# 4_324_039__3_1.net
KiCad netlist of a schematic drawn in Altium Designer
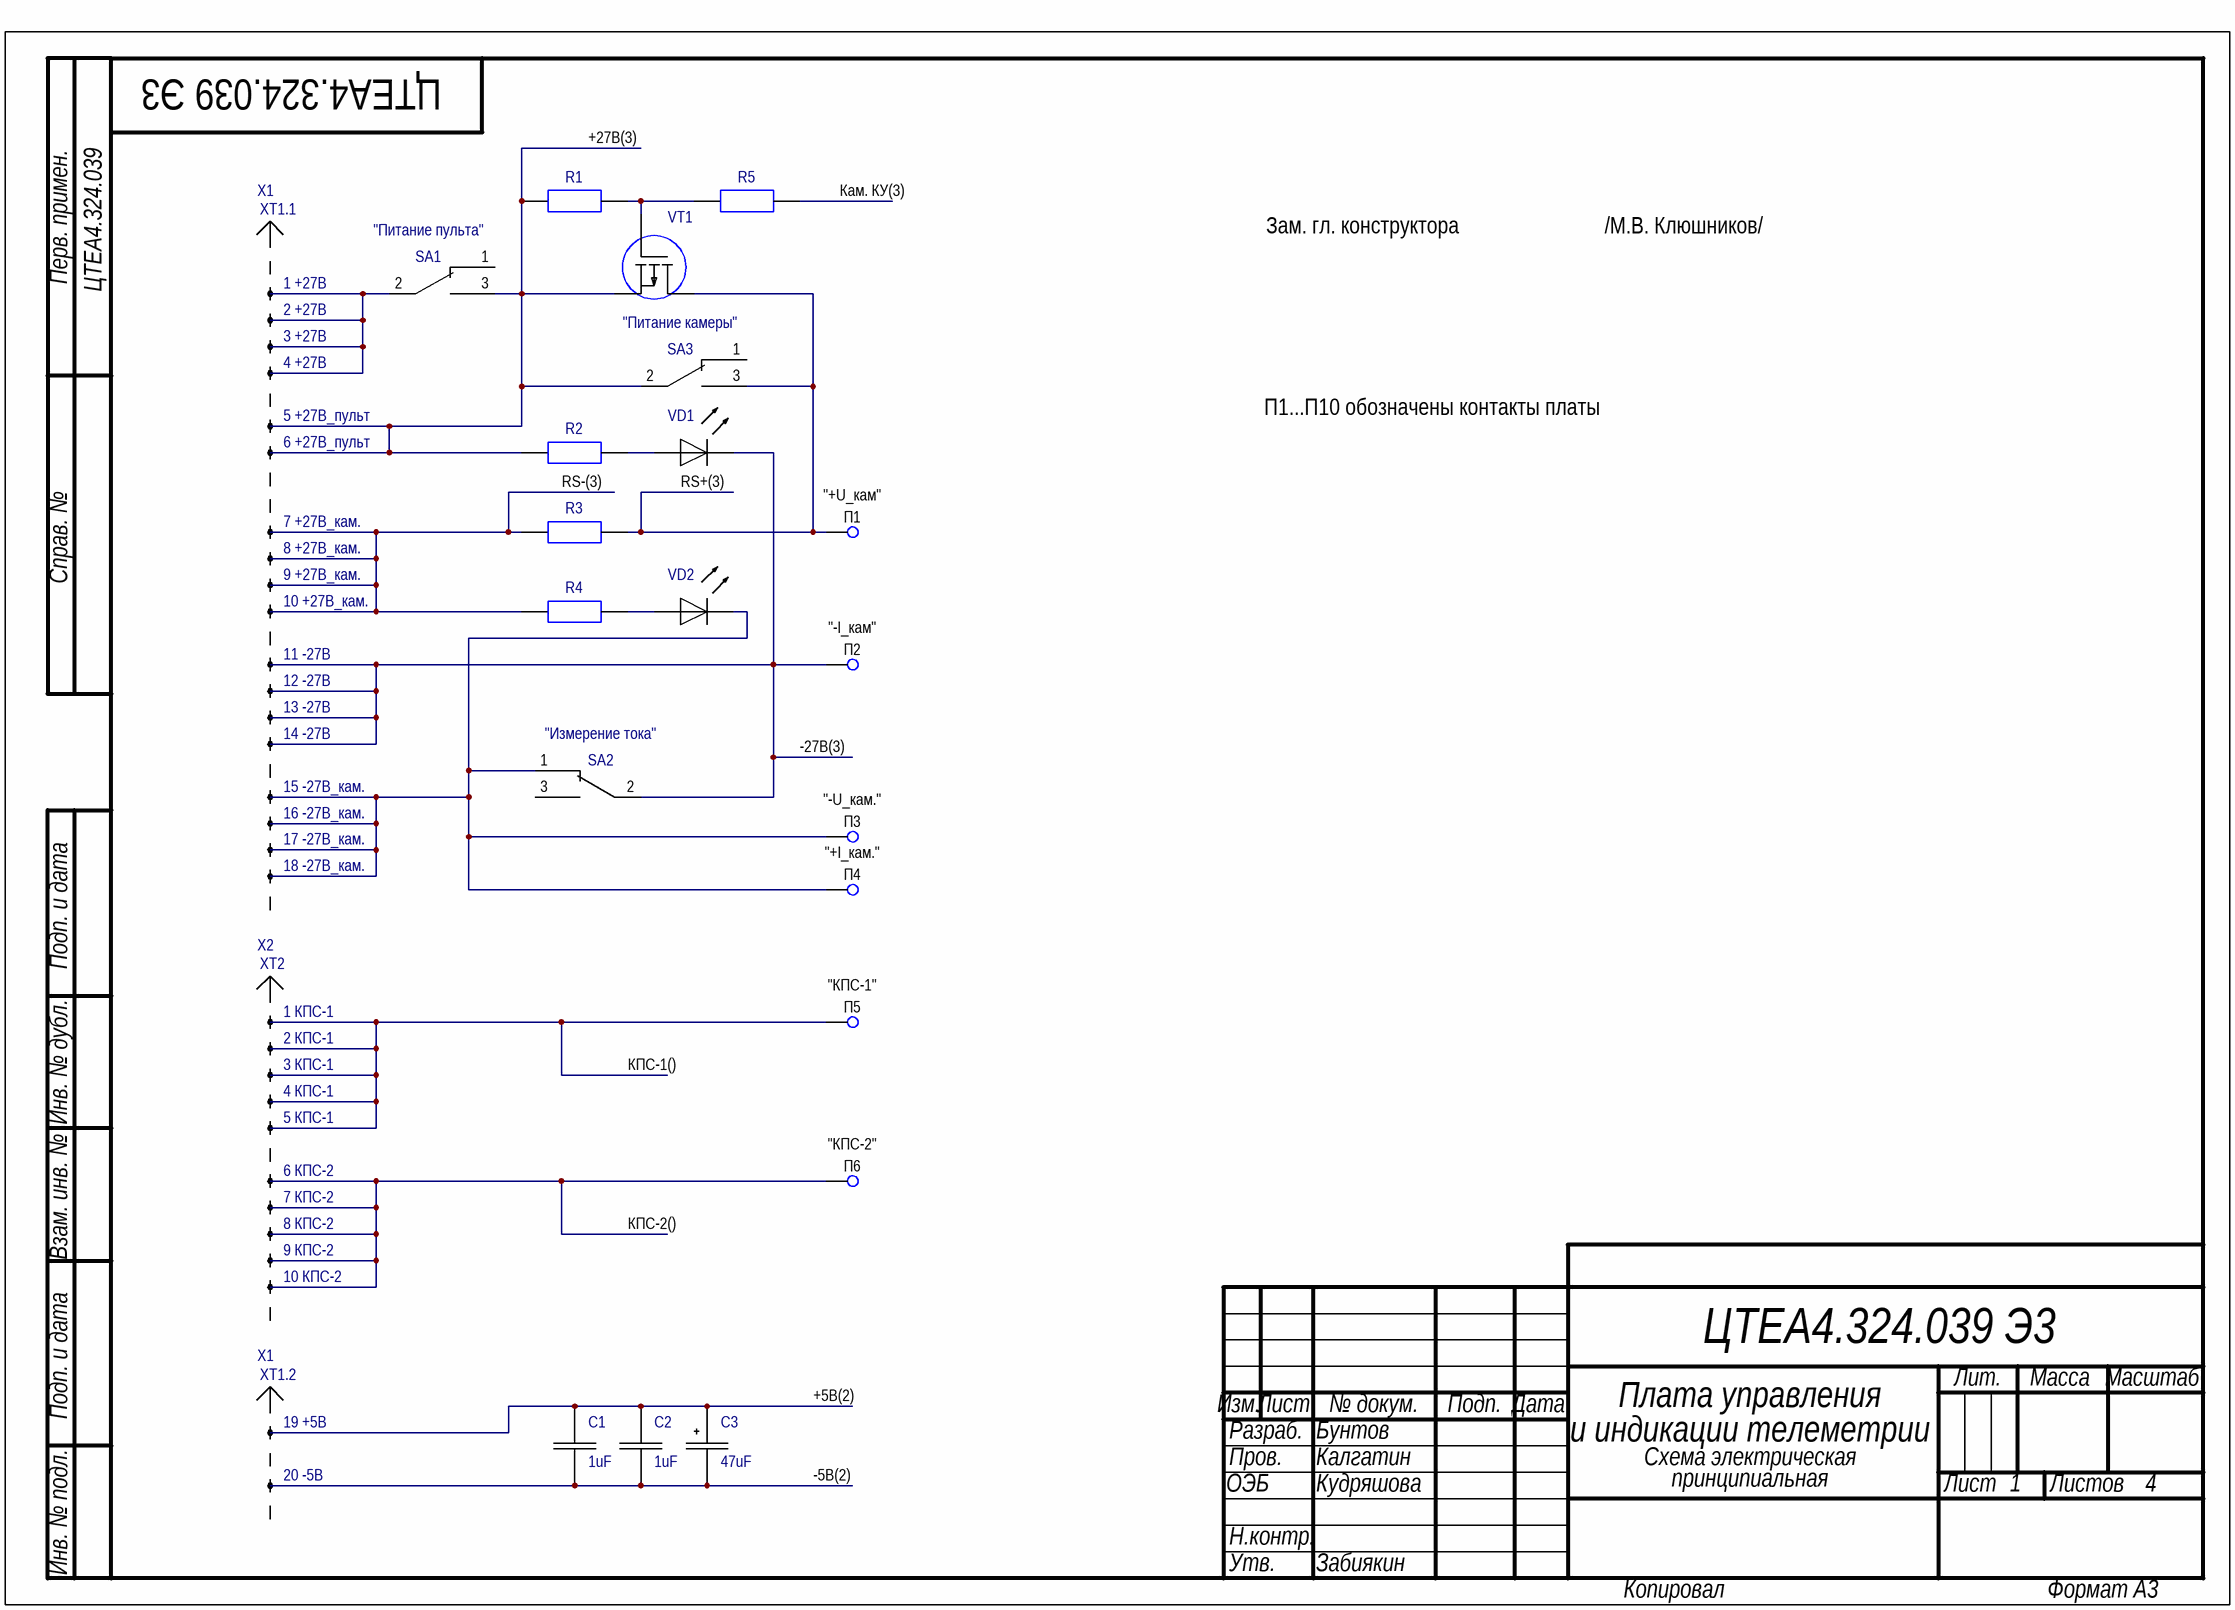
[diagram p0: ЦТЕА4.324.039_Э3_1.SchDoc]

(export (version "E")
  (design (tool "Eeschema 10.0.6"))
  (components
    (comp (ref "C1")
      (value "1uF")
      (footprint "GRM21BR61E105KA01K")
      (libsource (lib "GRM21BR61E105KA01K-3kl") (part "Condensator"))
    )
    (comp (ref "C2")
      (value "1uF")
      (footprint "GRM21BR61E105KA01K")
      (libsource (lib "GRM21BR61E105KA01K-3kl") (part "Condensator"))
    )
    (comp (ref "C3")
      (value "47uF")
      (footprint "TAJV686MO35RNJ")
      (libsource (lib "TAJV686MO35RNJ-3kl") (part "Condensator"))
    )
    (comp (ref "R1")
      (value "Res")
      (footprint "CR1206-JW-8250ELF")
      (libsource (lib "CR1206-JW-8250ELF-3kl") (part "Rezistor"))
    )
    (comp (ref "R2")
      (value "Res")
      (footprint "CR1206-JW-4701ELF")
      (libsource (lib "CR1206-JW-4701ELF-3kl") (part "Rezistor"))
    )
    (comp (ref "R3")
      (value "Res")
      (footprint "KNP100JTB0R1-1_0000_175")
      (libsource (lib "KNP100JTB0R1-f1-3kl") (part "Rezistor"))
    )
    (comp (ref "R4")
      (value "Res")
      (footprint "CR1206-JW-4701ELF")
      (libsource (lib "CR1206-JW-4701ELF-3kl") (part "Rezistor"))
    )
    (comp (ref "R5")
      (value "Res")
      (footprint "CR1206-JW-1001ELF")
      (libsource (lib "CR1206-JW-1001ELF-3kl") (part "Rezistor"))
    )
    (comp (ref "SA1")
      (value "\"Питание пульта\"")
      (footprint "7101SYZQE-3kl:7107SYZQE")
      (libsource (lib "7101SYZQE-3kl") (part "Perekljuchatel"))
    )
    (comp (ref "SA2")
      (value "\"Измерение тока\"")
      (footprint "7101SYZQE-3kl:7107SYZQE")
      (libsource (lib "7101SYZQE-3kl") (part "Perekljuchatel"))
    )
    (comp (ref "SA3")
      (value "\"Питание камеры\"")
      (footprint "7101SYZQE-3kl:7107SYZQE")
      (libsource (lib "7101SYZQE-3kl") (part "Perekljuchatel"))
    )
    (comp (ref "VD1")
      (value "LED")
      (footprint "HLMP-D150")
      (libsource (lib "HLMP-D150-3kl") (part "Svetodiod"))
    )
    (comp (ref "VD2")
      (value "LED")
      (footprint "HLMP-D150")
      (libsource (lib "HLMP-D150-3kl") (part "Svetodiod"))
    )
    (comp (ref "VT1")
      (value "IRF4905PBF")
      (footprint "IRF4905PBF-f1")
      (description "MOSFET")
      (libsource (lib "IRF4905PBF-3kl") (part "MOSFET-P"))
    )
    (comp (ref "XT1")
      (value "1 +27В")
      (footprint "PLD-20")
      (libsource (lib "PLD-20-3kl") (part "Razem shtyrevoj"))
    )
    (comp (ref "XT2")
      (value "1 КПС-1")
      (footprint "PLD-10")
      (libsource (lib "PLD-10-3kl") (part "Razem shtyrevoj"))
    )
    (comp (ref "П1")
      (value "\"+U_кам\"")
      (footprint "ZMP")
      (description "pad_ЗМП")
      (libsource (lib "ZMP-3kl") (part "Zazhim malogobaritnyj"))
    )
    (comp (ref "П2")
      (value "\"-I_кам\"")
      (footprint "ZMP")
      (description "pad_ЗМП")
      (libsource (lib "ZMP-3kl") (part "Zazhim malogobaritnyj"))
    )
    (comp (ref "П3")
      (value "\"-U_кам.\"")
      (footprint "ZMP")
      (description "pad_ЗМП")
      (libsource (lib "ZMP-3kl") (part "Zazhim malogobaritnyj"))
    )
    (comp (ref "П4")
      (value "\"+I_кам.\"")
      (footprint "ZMP")
      (description "pad_ЗМП")
      (libsource (lib "ZMP-3kl") (part "Zazhim malogobaritnyj"))
    )
    (comp (ref "П5")
      (value "\"КПС-1\"")
      (footprint "ZMP")
      (description "pad_ЗМП")
      (libsource (lib "ZMP-3kl") (part "Zazhim malogobaritnyj"))
    )
    (comp (ref "П6")
      (value "\"КПС-2\"")
      (footprint "ZMP")
      (description "pad_ЗМП")
      (libsource (lib "ZMP-3kl") (part "Zazhim malogobaritnyj"))
    )
  )
  (nets
    (net (code "1") (name "/+5V") (class "Default")
      (node (ref "C1") (pin "2") (pinfunction "2_2") (pintype "passive"))
      (node (ref "C2") (pin "2") (pinfunction "2_2") (pintype "passive"))
      (node (ref "C3") (pin "1") (pinfunction "1_1") (pintype "passive"))
      (node (ref "XT1") (pin "19") (pinfunction "19_19") (pintype "passive"))
    )
    (net (code "2") (name "/+27В") (class "Default")
      (node (ref "SA1") (pin "2") (pinfunction "2_2") (pintype "passive"))
      (node (ref "XT1") (pin "1") (pinfunction "1_1") (pintype "passive"))
      (node (ref "XT1") (pin "2") (pinfunction "2_2") (pintype "passive"))
      (node (ref "XT1") (pin "3") (pinfunction "3_3") (pintype "passive"))
      (node (ref "XT1") (pin "4") (pinfunction "4_4") (pintype "passive"))
    )
    (net (code "3") (name "/+27В_кам_RS+") (class "Default")
      (node (ref "R3") (pin "2") (pinfunction "2_2") (pintype "passive"))
      (node (ref "SA3") (pin "3") (pinfunction "3_3") (pintype "passive"))
      (node (ref "VT1") (pin "2") (pinfunction "D_2") (pintype "passive"))
      (node (ref "П1") (pin "1") (pinfunction "1_1") (pintype "passive"))
    )
    (net (code "4") (name "/+27В_кам_RS-") (class "Default")
      (node (ref "R3") (pin "1") (pinfunction "1_1") (pintype "passive"))
      (node (ref "R4") (pin "1") (pinfunction "1_1") (pintype "passive"))
      (node (ref "XT1") (pin "10") (pinfunction "10_10") (pintype "passive"))
      (node (ref "XT1") (pin "7") (pinfunction "7_7") (pintype "passive"))
      (node (ref "XT1") (pin "8") (pinfunction "8_8") (pintype "passive"))
      (node (ref "XT1") (pin "9") (pinfunction "9_9") (pintype "passive"))
    )
    (net (code "5") (name "/+27В_пульт") (class "Default")
      (node (ref "R1") (pin "1") (pinfunction "1_1") (pintype "passive"))
      (node (ref "R2") (pin "1") (pinfunction "1_1") (pintype "passive"))
      (node (ref "SA1") (pin "3") (pinfunction "3_3") (pintype "passive"))
      (node (ref "SA3") (pin "2") (pinfunction "2_2") (pintype "passive"))
      (node (ref "VT1") (pin "3") (pinfunction "S_3") (pintype "passive"))
      (node (ref "XT1") (pin "5") (pinfunction "5_5") (pintype "passive"))
      (node (ref "XT1") (pin "6") (pinfunction "6_6") (pintype "passive"))
    )
    (net (code "6") (name "/-27В") (class "Default")
      (node (ref "SA2") (pin "2") (pinfunction "2_2") (pintype "passive"))
      (node (ref "VD1") (pin "2") (pinfunction "C_2") (pintype "passive"))
      (node (ref "XT1") (pin "11") (pinfunction "11_11") (pintype "passive"))
      (node (ref "XT1") (pin "12") (pinfunction "12_12") (pintype "passive"))
      (node (ref "XT1") (pin "13") (pinfunction "13_13") (pintype "passive"))
      (node (ref "XT1") (pin "14") (pinfunction "14_14") (pintype "passive"))
      (node (ref "П2") (pin "1") (pinfunction "1_1") (pintype "passive"))
    )
    (net (code "7") (name "/-27В_камера") (class "Default")
      (node (ref "SA2") (pin "1") (pinfunction "1_1") (pintype "passive"))
      (node (ref "VD2") (pin "2") (pinfunction "C_2") (pintype "passive"))
      (node (ref "XT1") (pin "15") (pinfunction "15_15") (pintype "passive"))
      (node (ref "XT1") (pin "16") (pinfunction "16_16") (pintype "passive"))
      (node (ref "XT1") (pin "17") (pinfunction "17_17") (pintype "passive"))
      (node (ref "XT1") (pin "18") (pinfunction "18_18") (pintype "passive"))
      (node (ref "П3") (pin "1") (pinfunction "1_1") (pintype "passive"))
      (node (ref "П4") (pin "1") (pinfunction "1_1") (pintype "passive"))
    )
    (net (code "8") (name "/Cam_power") (class "Default")
      (node (ref "R5") (pin "2") (pinfunction "2_2") (pintype "passive"))
    )
    (net (code "9") (name "/GND") (class "Default")
      (node (ref "C1") (pin "1") (pinfunction "1_1") (pintype "passive"))
      (node (ref "C2") (pin "1") (pinfunction "1_1") (pintype "passive"))
      (node (ref "C3") (pin "2") (pinfunction "2_2") (pintype "passive"))
      (node (ref "XT1") (pin "20") (pinfunction "20_20") (pintype "passive"))
    )
    (net (code "10") (name "/КПС-1") (class "Default")
      (node (ref "XT2") (pin "1") (pinfunction "1_1") (pintype "passive"))
      (node (ref "XT2") (pin "2") (pinfunction "2_2") (pintype "passive"))
      (node (ref "XT2") (pin "3") (pinfunction "3_3") (pintype "passive"))
      (node (ref "XT2") (pin "4") (pinfunction "4_4") (pintype "passive"))
      (node (ref "XT2") (pin "5") (pinfunction "5_5") (pintype "passive"))
      (node (ref "П5") (pin "1") (pinfunction "1_1") (pintype "passive"))
    )
    (net (code "11") (name "/КПС-2") (class "Default")
      (node (ref "XT2") (pin "10") (pinfunction "10_10") (pintype "passive"))
      (node (ref "XT2") (pin "6") (pinfunction "6_6") (pintype "passive"))
      (node (ref "XT2") (pin "7") (pinfunction "7_7") (pintype "passive"))
      (node (ref "XT2") (pin "8") (pinfunction "8_8") (pintype "passive"))
      (node (ref "XT2") (pin "9") (pinfunction "9_9") (pintype "passive"))
      (node (ref "П6") (pin "1") (pinfunction "1_1") (pintype "passive"))
    )
    (net (code "12") (name "Net-(VD1-A)") (class "Default")
      (node (ref "R2") (pin "2") (pinfunction "2_2") (pintype "passive"))
      (node (ref "VD1") (pin "1") (pinfunction "A_1") (pintype "passive"))
    )
    (net (code "13") (name "Net-(VD2-A)") (class "Default")
      (node (ref "R4") (pin "2") (pinfunction "2_2") (pintype "passive"))
      (node (ref "VD2") (pin "1") (pinfunction "A_1") (pintype "passive"))
    )
    (net (code "14") (name "Net-(VT1-G)") (class "Default")
      (node (ref "R1") (pin "2") (pinfunction "2_2") (pintype "passive"))
      (node (ref "R5") (pin "1") (pinfunction "1_1") (pintype "passive"))
      (node (ref "VT1") (pin "1") (pinfunction "G_1") (pintype "passive"))
    )
    (net (code "15") (name "unconnected-(SA1-Pad1)") (class "Default")
      (node (ref "SA1") (pin "1") (pinfunction "1_1") (pintype "passive"))
    )
    (net (code "16") (name "unconnected-(SA2-Pad3)") (class "Default")
      (node (ref "SA2") (pin "3") (pinfunction "3_3") (pintype "passive"))
    )
    (net (code "17") (name "unconnected-(SA3-Pad1)") (class "Default")
      (node (ref "SA3") (pin "1") (pinfunction "1_1") (pintype "passive"))
    )
  )
)
